# Fetch_Execution_Counter_Electronic_Sheme.net
KiCad netlist of a schematic drawn in Altium Designer
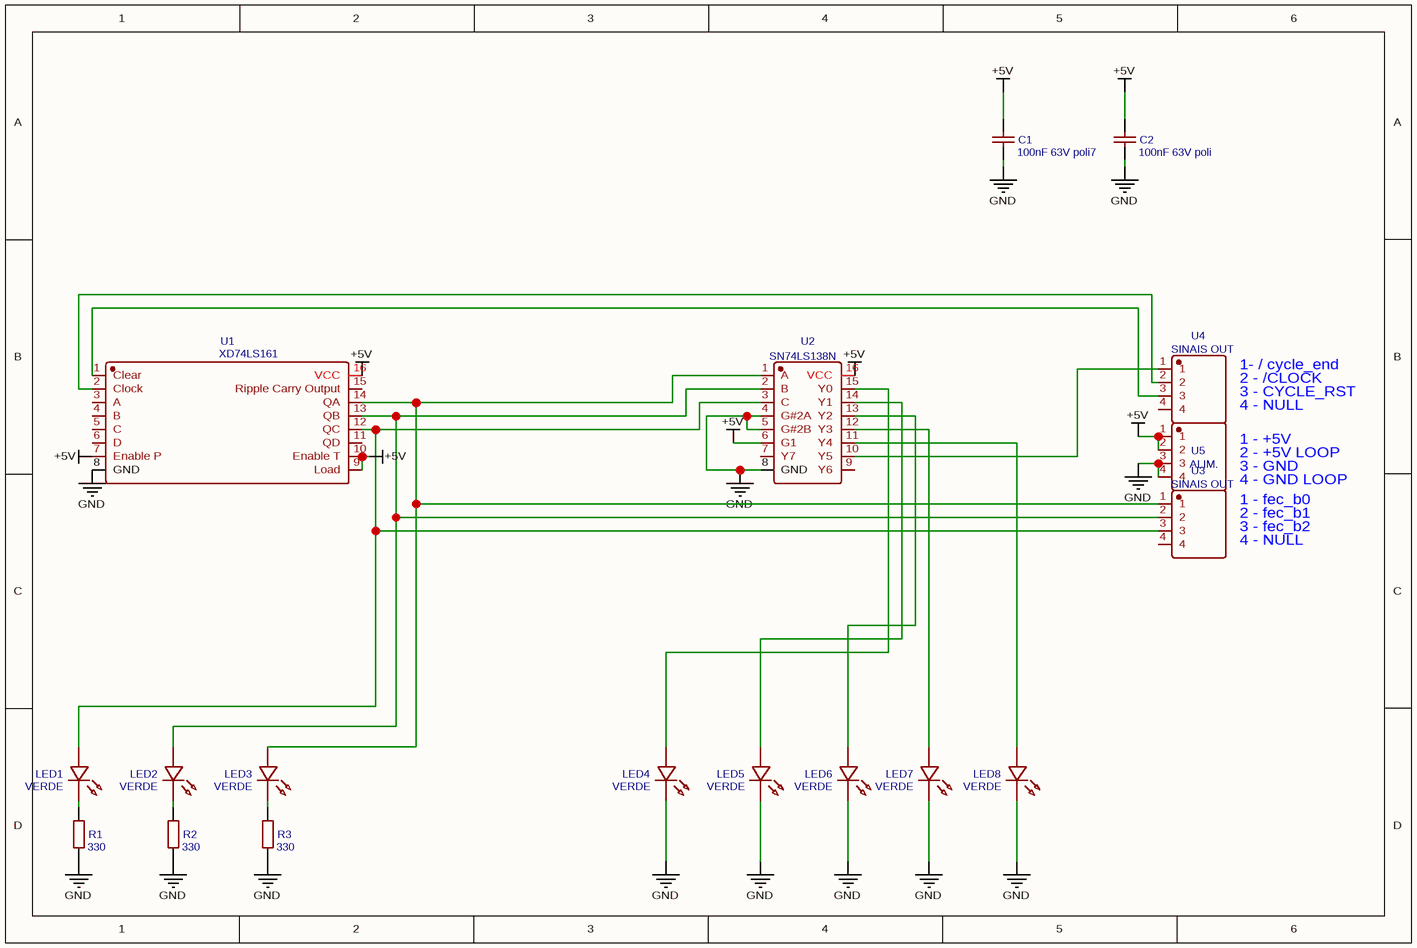
[diagram p0: Fetch Execution Counter Electronic Sheme_2021-10-10.schdoc]

(export (version "E")
  (design (tool "Eeschema 10.0.6"))
  (components
    (comp (ref "C1")
      (value "100nF 63V poli7")
      (fields
        (field (name "BOM_SUPPLIER PART") "C444741")
        (field (name "BOM_MANUFACTURER PART") "SR305C105KAR")
        (field (name "CONTRIBUTOR") "LCSC")
      )
      (libsource (lib "altium-import") (part "root_3_100nF 63V poli7_"))
    )
    (comp (ref "C2")
      (value "100nF 63V poli")
      (fields
        (field (name "BOM_SUPPLIER PART") "C444741")
        (field (name "BOM_MANUFACTURER PART") "SR305C105KAR")
        (field (name "CONTRIBUTOR") "LCSC")
      )
      (libsource (lib "altium-import") (part "root_3_100nF 63V poli_"))
    )
    (comp (ref "LED1")
      (value "VERDE")
      (fields
        (field (name "BOM_SUPPLIER PART") "C605465")
        (field (name "BOM_MANUFACTURER PART") "264-7GD")
        (field (name "CONTRIBUTOR") "LCSC")
      )
      (libsource (lib "altium-import") (part "root_1_VERDE_"))
    )
    (comp (ref "LED2")
      (value "VERDE")
      (fields
        (field (name "BOM_SUPPLIER PART") "C605465")
        (field (name "BOM_MANUFACTURER PART") "264-7GD")
        (field (name "CONTRIBUTOR") "LCSC")
      )
      (libsource (lib "altium-import") (part "root_1_VERDE_"))
    )
    (comp (ref "LED3")
      (value "VERDE")
      (fields
        (field (name "BOM_SUPPLIER PART") "C605465")
        (field (name "BOM_MANUFACTURER PART") "264-7GD")
        (field (name "CONTRIBUTOR") "LCSC")
      )
      (libsource (lib "altium-import") (part "root_1_VERDE_"))
    )
    (comp (ref "LED4")
      (value "VERDE")
      (fields
        (field (name "BOM_SUPPLIER PART") "C605465")
        (field (name "BOM_MANUFACTURER PART") "264-7GD")
        (field (name "CONTRIBUTOR") "LCSC")
      )
      (libsource (lib "altium-import") (part "root_1_VERDE_"))
    )
    (comp (ref "LED5")
      (value "VERDE")
      (fields
        (field (name "BOM_SUPPLIER PART") "C605465")
        (field (name "BOM_MANUFACTURER PART") "264-7GD")
        (field (name "CONTRIBUTOR") "LCSC")
      )
      (libsource (lib "altium-import") (part "root_1_VERDE_"))
    )
    (comp (ref "LED6")
      (value "VERDE")
      (fields
        (field (name "BOM_SUPPLIER PART") "C605465")
        (field (name "BOM_MANUFACTURER PART") "264-7GD")
        (field (name "CONTRIBUTOR") "LCSC")
      )
      (libsource (lib "altium-import") (part "root_1_VERDE_"))
    )
    (comp (ref "LED7")
      (value "VERDE")
      (fields
        (field (name "BOM_SUPPLIER PART") "C605465")
        (field (name "BOM_MANUFACTURER PART") "264-7GD")
        (field (name "CONTRIBUTOR") "LCSC")
      )
      (libsource (lib "altium-import") (part "root_1_VERDE_"))
    )
    (comp (ref "LED8")
      (value "VERDE")
      (fields
        (field (name "BOM_SUPPLIER PART") "C605465")
        (field (name "BOM_MANUFACTURER PART") "264-7GD")
        (field (name "CONTRIBUTOR") "LCSC")
      )
      (libsource (lib "altium-import") (part "root_1_VERDE_"))
    )
    (comp (ref "R1")
      (value "330")
      (fields
        (field (name "BOM_MANUFACTURER PART") "CFR02SJ0823A10")
        (field (name "BOM_SUPPLIER PART") "C69876")
      )
      (libsource (lib "altium-import") (part "root_3_330_"))
    )
    (comp (ref "R2")
      (value "330")
      (fields
        (field (name "BOM_MANUFACTURER PART") "CFR02SJ0823A10")
        (field (name "BOM_SUPPLIER PART") "C69876")
      )
      (libsource (lib "altium-import") (part "root_3_330_"))
    )
    (comp (ref "R3")
      (value "330")
      (fields
        (field (name "BOM_MANUFACTURER PART") "CFR02SJ0823A10")
        (field (name "BOM_SUPPLIER PART") "C69876")
      )
      (libsource (lib "altium-import") (part "root_3_330_"))
    )
    (comp (ref "U1")
      (value "XD74LS161")
      (fields (field (name "BOM_SUPPLIER PART") "C609766") (field (name "CONTRIBUTOR") "LCSC"))
      (libsource (lib "altium-import") (part "root_0_XD74LS161_"))
    )
    (comp (ref "U2")
      (value "SN74LS138N")
      (fields (field (name "BOM_SUPPLIER PART") "C352964") (field (name "CONTRIBUTOR") "LCSC"))
      (libsource (lib "altium-import") (part "root_0_SN74LS138N_"))
    )
    (comp (ref "U3")
      (value "SINAIS OUT")
      (fields
        (field (name "BOM_SUPPLIER PART") "C210162")
        (field (name "BOM_MANUFACTURER PART") "171825-4")
        (field (name "CONTRIBUTOR") "LCSC")
      )
      (libsource (lib "altium-import") (part "root_0_SINAIS OUT_"))
    )
    (comp (ref "U4")
      (value "SINAIS OUT")
      (fields
        (field (name "BOM_SUPPLIER PART") "C210162")
        (field (name "BOM_MANUFACTURER PART") "171825-4")
        (field (name "CONTRIBUTOR") "LCSC")
      )
      (libsource (lib "altium-import") (part "root_0_SINAIS OUT_"))
    )
    (comp (ref "U5")
      (value "ALIM.")
      (fields
        (field (name "BOM_SUPPLIER PART") "C210162")
        (field (name "BOM_MANUFACTURER PART") "171825-4")
        (field (name "CONTRIBUTOR") "LCSC")
      )
      (libsource (lib "altium-import") (part "root_0_ALIM._"))
    )
  )
  (nets
    (net (code "1") (name "+5V") (class "Default")
      (node (ref "C1") (pin "1") (pinfunction "1_1") (pintype "passive"))
      (node (ref "C2") (pin "1") (pinfunction "1_1") (pintype "passive"))
      (node (ref "U1") (pin "10") (pinfunction "Enable_T_10") (pintype "passive"))
      (node (ref "U1") (pin "16") (pinfunction "VCC_16") (pintype "passive"))
      (node (ref "U1") (pin "7") (pinfunction "Enable_P_7") (pintype "passive"))
      (node (ref "U1") (pin "9") (pinfunction "Load_9") (pintype "passive"))
      (node (ref "U2") (pin "16") (pinfunction "VCC_16") (pintype "passive"))
      (node (ref "U2") (pin "6") (pinfunction "G1_6") (pintype "passive"))
      (node (ref "U5") (pin "1") (pinfunction "1_1") (pintype "passive"))
      (node (ref "U5") (pin "2") (pinfunction "2_2") (pintype "passive"))
    )
    (net (code "2") (name "GND") (class "Default")
      (node (ref "C1") (pin "2") (pinfunction "2_2") (pintype "passive"))
      (node (ref "C2") (pin "2") (pinfunction "2_2") (pintype "passive"))
      (node (ref "LED4") (pin "1") (pinfunction "-_1") (pintype "passive"))
      (node (ref "LED5") (pin "1") (pinfunction "-_1") (pintype "passive"))
      (node (ref "LED6") (pin "1") (pinfunction "-_1") (pintype "passive"))
      (node (ref "LED7") (pin "1") (pinfunction "-_1") (pintype "passive"))
      (node (ref "LED8") (pin "1") (pinfunction "-_1") (pintype "passive"))
      (node (ref "R1") (pin "2") (pinfunction "2_2") (pintype "passive"))
      (node (ref "R2") (pin "2") (pinfunction "2_2") (pintype "passive"))
      (node (ref "R3") (pin "2") (pinfunction "2_2") (pintype "passive"))
      (node (ref "U1") (pin "8") (pinfunction "GND_8") (pintype "passive"))
      (node (ref "U2") (pin "4") (pinfunction "G#2A_4") (pintype "passive"))
      (node (ref "U2") (pin "5") (pinfunction "G#2B_5") (pintype "passive"))
      (node (ref "U2") (pin "8") (pinfunction "GND_8") (pintype "passive"))
      (node (ref "U5") (pin "3") (pinfunction "3_3") (pintype "passive"))
      (node (ref "U5") (pin "4") (pinfunction "4_4") (pintype "passive"))
    )
    (net (code "3") (name "Net-(LED1-+)") (class "Default")
      (node (ref "LED1") (pin "2") (pinfunction "+_2") (pintype "passive"))
      (node (ref "U1") (pin "12") (pinfunction "QC_12") (pintype "passive"))
      (node (ref "U2") (pin "3") (pinfunction "C_3") (pintype "passive"))
      (node (ref "U3") (pin "3") (pinfunction "3_3") (pintype "passive"))
    )
    (net (code "4") (name "Net-(LED1--)") (class "Default")
      (node (ref "LED1") (pin "1") (pinfunction "-_1") (pintype "passive"))
      (node (ref "R1") (pin "1") (pinfunction "1_1") (pintype "passive"))
    )
    (net (code "5") (name "Net-(LED2-+)") (class "Default")
      (node (ref "LED2") (pin "2") (pinfunction "+_2") (pintype "passive"))
      (node (ref "U1") (pin "13") (pinfunction "QB_13") (pintype "passive"))
      (node (ref "U2") (pin "2") (pinfunction "B_2") (pintype "passive"))
      (node (ref "U3") (pin "2") (pinfunction "2_2") (pintype "passive"))
    )
    (net (code "6") (name "Net-(LED2--)") (class "Default")
      (node (ref "LED2") (pin "1") (pinfunction "-_1") (pintype "passive"))
      (node (ref "R2") (pin "1") (pinfunction "1_1") (pintype "passive"))
    )
    (net (code "7") (name "Net-(LED3-+)") (class "Default")
      (node (ref "LED3") (pin "2") (pinfunction "+_2") (pintype "passive"))
      (node (ref "U1") (pin "14") (pinfunction "QA_14") (pintype "passive"))
      (node (ref "U2") (pin "1") (pinfunction "A_1") (pintype "passive"))
      (node (ref "U3") (pin "1") (pinfunction "1_1") (pintype "passive"))
    )
    (net (code "8") (name "Net-(LED3--)") (class "Default")
      (node (ref "LED3") (pin "1") (pinfunction "-_1") (pintype "passive"))
      (node (ref "R3") (pin "1") (pinfunction "1_1") (pintype "passive"))
    )
    (net (code "9") (name "Net-(LED4-+)") (class "Default")
      (node (ref "LED4") (pin "2") (pinfunction "+_2") (pintype "passive"))
      (node (ref "U2") (pin "15") (pinfunction "Y0_15") (pintype "passive"))
    )
    (net (code "10") (name "Net-(LED5-+)") (class "Default")
      (node (ref "LED5") (pin "2") (pinfunction "+_2") (pintype "passive"))
      (node (ref "U2") (pin "14") (pinfunction "Y1_14") (pintype "passive"))
    )
    (net (code "11") (name "Net-(LED6-+)") (class "Default")
      (node (ref "LED6") (pin "2") (pinfunction "+_2") (pintype "passive"))
      (node (ref "U2") (pin "13") (pinfunction "Y2_13") (pintype "passive"))
    )
    (net (code "12") (name "Net-(LED7-+)") (class "Default")
      (node (ref "LED7") (pin "2") (pinfunction "+_2") (pintype "passive"))
      (node (ref "U2") (pin "12") (pinfunction "Y3_12") (pintype "passive"))
    )
    (net (code "13") (name "Net-(LED8-+)") (class "Default")
      (node (ref "LED8") (pin "2") (pinfunction "+_2") (pintype "passive"))
      (node (ref "U2") (pin "11") (pinfunction "Y4_11") (pintype "passive"))
    )
    (net (code "14") (name "Net-(U1-Clear)") (class "Default")
      (node (ref "U1") (pin "1") (pinfunction "Clear_1") (pintype "passive"))
      (node (ref "U4") (pin "3") (pinfunction "3_3") (pintype "passive"))
    )
    (net (code "15") (name "Net-(U1-Clock)") (class "Default")
      (node (ref "U1") (pin "2") (pinfunction "Clock_2") (pintype "passive"))
      (node (ref "U4") (pin "2") (pinfunction "2_2") (pintype "passive"))
    )
    (net (code "16") (name "Net-(U2-Y5)") (class "Default")
      (node (ref "U2") (pin "10") (pinfunction "Y5_10") (pintype "passive"))
      (node (ref "U4") (pin "1") (pinfunction "1_1") (pintype "passive"))
    )
    (net (code "17") (name "unconnected-(U1-A-Pad3)") (class "Default")
      (node (ref "U1") (pin "3") (pinfunction "A_3") (pintype "passive"))
    )
    (net (code "18") (name "unconnected-(U1-B-Pad4)") (class "Default")
      (node (ref "U1") (pin "4") (pinfunction "B_4") (pintype "passive"))
    )
    (net (code "19") (name "unconnected-(U1-C-Pad5)") (class "Default")
      (node (ref "U1") (pin "5") (pinfunction "C_5") (pintype "passive"))
    )
    (net (code "20") (name "unconnected-(U1-D-Pad6)") (class "Default")
      (node (ref "U1") (pin "6") (pinfunction "D_6") (pintype "passive"))
    )
    (net (code "21") (name "unconnected-(U1-QD-Pad11)") (class "Default")
      (node (ref "U1") (pin "11") (pinfunction "QD_11") (pintype "passive"))
    )
    (net (code "22") (name "unconnected-(U1-Ripple_Carry_Output-Pad15)") (class "Default")
      (node (ref "U1") (pin "15") (pinfunction "Ripple_Carry_Output_15") (pintype "passive"))
    )
    (net (code "23") (name "unconnected-(U2-Y6-Pad9)") (class "Default")
      (node (ref "U2") (pin "9") (pinfunction "Y6_9") (pintype "passive"))
    )
    (net (code "24") (name "unconnected-(U2-Y7-Pad7)") (class "Default")
      (node (ref "U2") (pin "7") (pinfunction "Y7_7") (pintype "passive"))
    )
    (net (code "25") (name "unconnected-(U3-Pad4)") (class "Default")
      (node (ref "U3") (pin "4") (pinfunction "4_4") (pintype "passive"))
    )
    (net (code "26") (name "unconnected-(U4-Pad4)") (class "Default")
      (node (ref "U4") (pin "4") (pinfunction "4_4") (pintype "passive"))
    )
  )
)
